# UPDuino_Camera_Adapter_2_himax.net
KiCad netlist of a schematic drawn in EAGLE
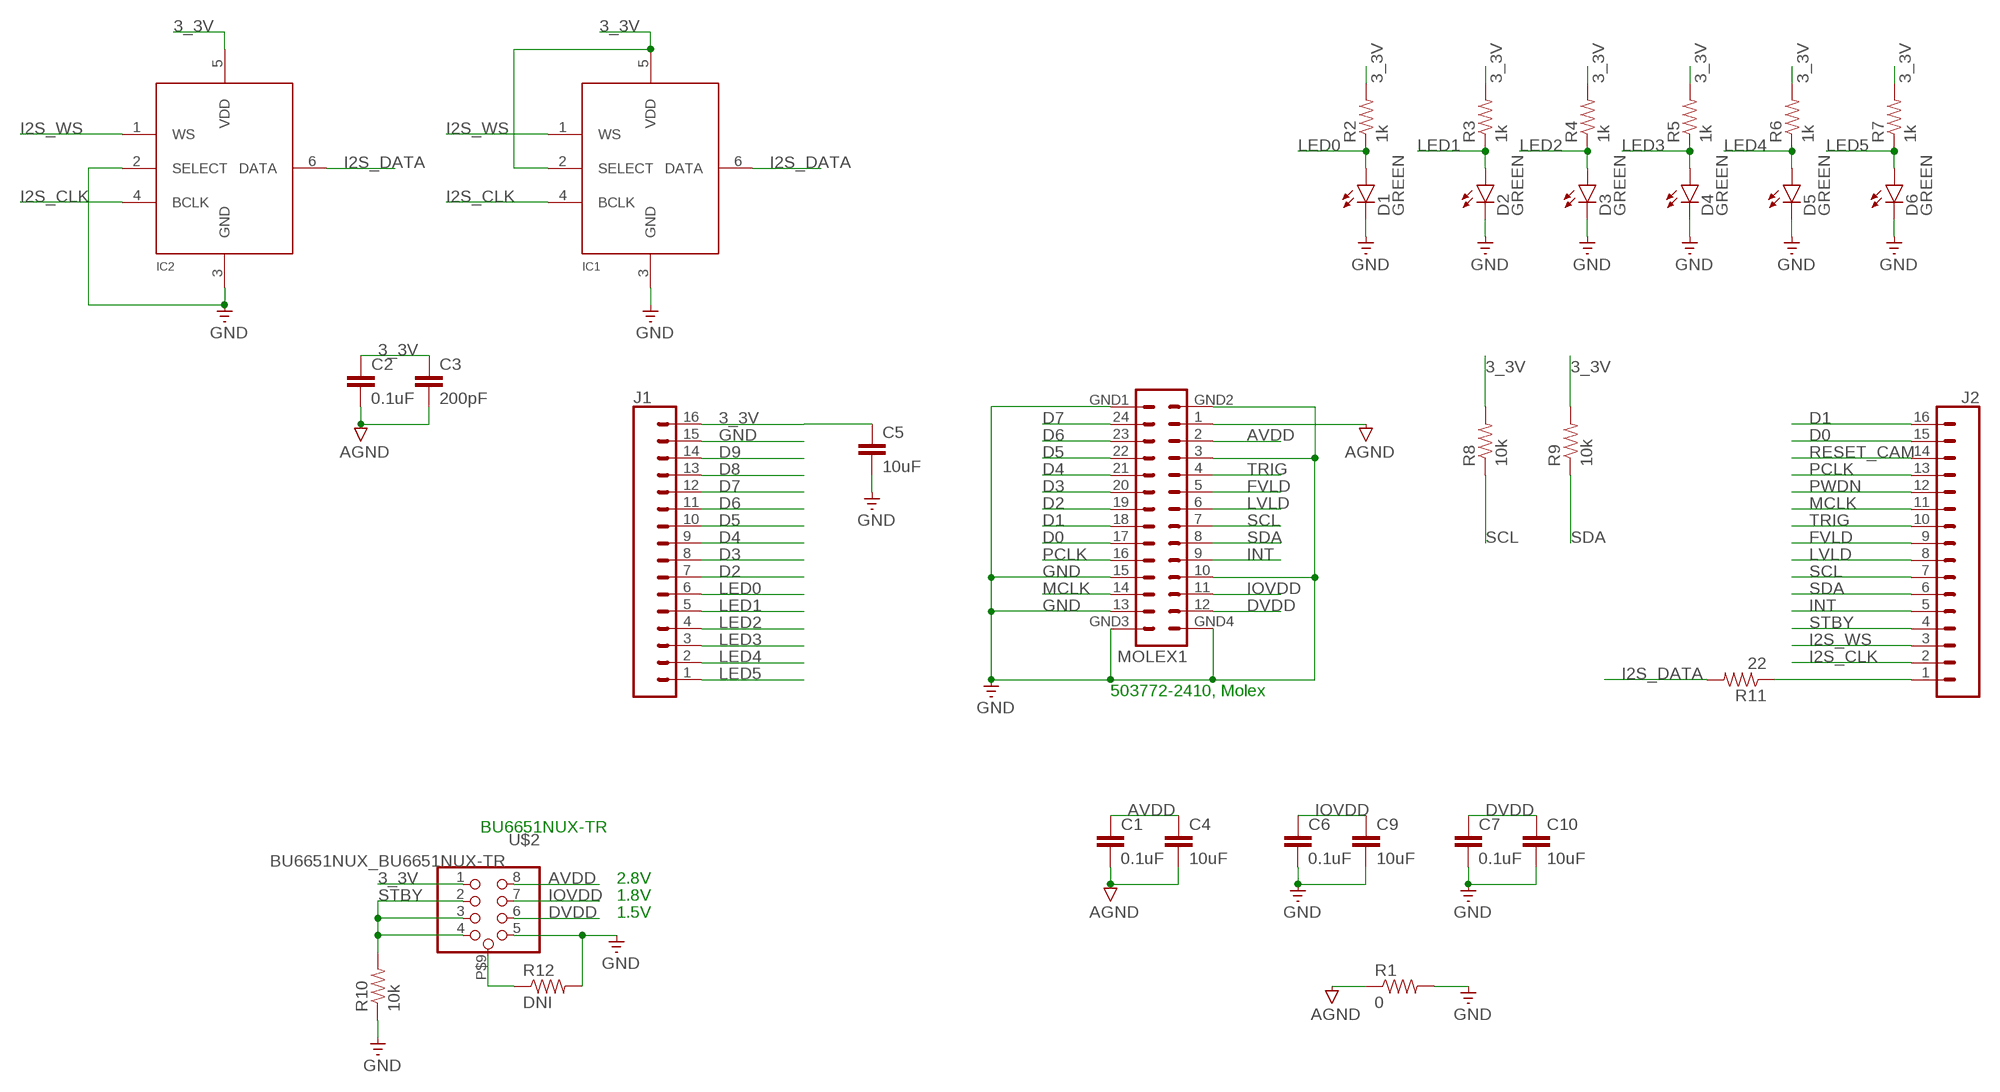
[diagram p0: schematic, sheet 1]

(export (version "E")
  (design (tool "Eeschema 10.0.6"))
  (components
    (comp (ref "C1")
      (value "0.1uF")
      (footprint "eagle-import:0603")
      (libsource (lib "eagle-import") (part "0.1UF-0603-25V-(+80/-20%)"))
    )
    (comp (ref "C2")
      (value "0.1uF")
      (footprint "eagle-import:0603")
      (libsource (lib "eagle-import") (part "0.1UF-0603-25V-(+80/-20%)"))
    )
    (comp (ref "C3")
      (value "200pF")
      (footprint "eagle-import:0603")
      (libsource (lib "eagle-import") (part "10UF-0603-6.3V-20%"))
    )
    (comp (ref "C4")
      (value "10uF")
      (footprint "eagle-import:0603")
      (libsource (lib "eagle-import") (part "10UF-0603-6.3V-20%"))
    )
    (comp (ref "C5")
      (value "10uF")
      (footprint "eagle-import:0603")
      (libsource (lib "eagle-import") (part "10UF-0603-6.3V-20%"))
    )
    (comp (ref "C6")
      (value "0.1uF")
      (footprint "eagle-import:0603")
      (libsource (lib "eagle-import") (part "0.1UF-0603-25V-(+80/-20%)"))
    )
    (comp (ref "C7")
      (value "0.1uF")
      (footprint "eagle-import:0603")
      (libsource (lib "eagle-import") (part "0.1UF-0603-25V-(+80/-20%)"))
    )
    (comp (ref "C9")
      (value "10uF")
      (footprint "eagle-import:0603")
      (libsource (lib "eagle-import") (part "10UF-0603-6.3V-20%"))
    )
    (comp (ref "C10")
      (value "10uF")
      (footprint "eagle-import:0603")
      (libsource (lib "eagle-import") (part "10UF-0603-6.3V-20%"))
    )
    (comp (ref "D1")
      (value "GREEN")
      (footprint "eagle-import:LED-0603")
      (libsource (lib "eagle-import") (part "LED-GREEN0603"))
    )
    (comp (ref "D2")
      (value "GREEN")
      (footprint "eagle-import:LED-0603")
      (libsource (lib "eagle-import") (part "LED-GREEN0603"))
    )
    (comp (ref "D3")
      (value "GREEN")
      (footprint "eagle-import:LED-0603")
      (libsource (lib "eagle-import") (part "LED-GREEN0603"))
    )
    (comp (ref "D4")
      (value "GREEN")
      (footprint "eagle-import:LED-0603")
      (libsource (lib "eagle-import") (part "LED-GREEN0603"))
    )
    (comp (ref "D5")
      (value "GREEN")
      (footprint "eagle-import:LED-0603")
      (libsource (lib "eagle-import") (part "LED-GREEN0603"))
    )
    (comp (ref "D6")
      (value "GREEN")
      (footprint "eagle-import:LED-0603")
      (libsource (lib "eagle-import") (part "LED-GREEN0603"))
    )
    (comp (ref "IC1")
      (value "MIC_I2S_SPH0645")
      (footprint "eagle-import:SPH0645LM4H")
      (libsource (lib "eagle-import") (part "MIC_I2S_SPH0645"))
    )
    (comp (ref "IC2")
      (value "MIC_I2S_SPH0645")
      (footprint "eagle-import:SPH0645LM4H")
      (libsource (lib "eagle-import") (part "MIC_I2S_SPH0645"))
    )
    (comp (ref "J1")
      (value "CONN_16")
      (footprint "eagle-import:1X16")
      (libsource (lib "eagle-import") (part "CONN_16"))
    )
    (comp (ref "J2")
      (value "CONN_16")
      (footprint "eagle-import:1X16")
      (libsource (lib "eagle-import") (part "CONN_16"))
    )
    (comp (ref "MOLEX1")
      (value "MOLEX-5037722410_MOLEX")
      (footprint "eagle-import:MOLEX-5037722410_MOLEX")
      (libsource (lib "eagle-import") (part "MOLEX-5037722410_MOLEX"))
    )
    (comp (ref "R1")
      (value "0")
      (footprint "eagle-import:0603-RES")
      (libsource (lib "eagle-import") (part "RESISTOR0603"))
    )
    (comp (ref "R2")
      (value "1k")
      (footprint "eagle-import:0603-RES")
      (libsource (lib "eagle-import") (part "RESISTOR0603"))
    )
    (comp (ref "R3")
      (value "1k")
      (footprint "eagle-import:0603-RES")
      (libsource (lib "eagle-import") (part "RESISTOR0603"))
    )
    (comp (ref "R4")
      (value "1k")
      (footprint "eagle-import:0603-RES")
      (libsource (lib "eagle-import") (part "RESISTOR0603"))
    )
    (comp (ref "R5")
      (value "1k")
      (footprint "eagle-import:0603-RES")
      (libsource (lib "eagle-import") (part "RESISTOR0603"))
    )
    (comp (ref "R6")
      (value "1k")
      (footprint "eagle-import:0603-RES")
      (libsource (lib "eagle-import") (part "RESISTOR0603"))
    )
    (comp (ref "R7")
      (value "1k")
      (footprint "eagle-import:0603-RES")
      (libsource (lib "eagle-import") (part "RESISTOR0603"))
    )
    (comp (ref "R8")
      (value "10k")
      (footprint "eagle-import:0603-RES")
      (libsource (lib "eagle-import") (part "RESISTOR0603"))
    )
    (comp (ref "R9")
      (value "10k")
      (footprint "eagle-import:0603-RES")
      (libsource (lib "eagle-import") (part "RESISTOR0603"))
    )
    (comp (ref "R10")
      (value "10k")
      (footprint "eagle-import:0603-RES")
      (libsource (lib "eagle-import") (part "RESISTOR0603"))
    )
    (comp (ref "R11")
      (value "22")
      (footprint "eagle-import:0603-RES")
      (libsource (lib "eagle-import") (part "RESISTOR0603"))
    )
    (comp (ref "R12")
      (value "DNI")
      (footprint "eagle-import:0603-RES")
      (libsource (lib "eagle-import") (part "RESISTOR0603"))
    )
    (comp (ref "U$2")
      (value "BU6651NUX_BU6651NUX-TR")
      (footprint "eagle-import:BU6651NUX_BU6651NUX-TR")
      (libsource (lib "eagle-import") (part "BU6651NUX_BU6651NUX-TR"))
    )
  )
  (nets
    (net (code "1") (name "/3_3V") (class "Default")
      (node (ref "C2") (pin "1") (pinfunction "1_1") (pintype "passive"))
      (node (ref "C3") (pin "1") (pinfunction "1_1") (pintype "passive"))
      (node (ref "C5") (pin "1") (pinfunction "1_1") (pintype "passive"))
      (node (ref "IC1") (pin "2") (pinfunction "SELECT_2") (pintype "input"))
      (node (ref "IC1") (pin "5") (pinfunction "VDD_5") (pintype "power_in"))
      (node (ref "IC2") (pin "5") (pinfunction "VDD_5") (pintype "power_in"))
      (node (ref "J1") (pin "16") (pinfunction "16_16") (pintype "passive"))
      (node (ref "R2") (pin "2") (pinfunction "2_2") (pintype "passive"))
      (node (ref "R3") (pin "2") (pinfunction "2_2") (pintype "passive"))
      (node (ref "R4") (pin "2") (pinfunction "2_2") (pintype "passive"))
      (node (ref "R5") (pin "2") (pinfunction "2_2") (pintype "passive"))
      (node (ref "R6") (pin "2") (pinfunction "2_2") (pintype "passive"))
      (node (ref "R7") (pin "2") (pinfunction "2_2") (pintype "passive"))
      (node (ref "R8") (pin "2") (pinfunction "2_2") (pintype "passive"))
      (node (ref "R9") (pin "2") (pinfunction "2_2") (pintype "passive"))
      (node (ref "U$2") (pin "1") (pinfunction "8_1") (pintype "passive"))
    )
    (net (code "2") (name "/AVDD") (class "Default")
      (node (ref "C1") (pin "1") (pinfunction "1_1") (pintype "passive"))
      (node (ref "C4") (pin "1") (pinfunction "1_1") (pintype "passive"))
      (node (ref "MOLEX1") (pin "2") (pinfunction "2_2") (pintype "passive"))
      (node (ref "U$2") (pin "8") (pinfunction "1_8") (pintype "passive"))
    )
    (net (code "3") (name "/D0") (class "Default")
      (node (ref "J2") (pin "15") (pinfunction "15_15") (pintype "passive"))
      (node (ref "MOLEX1") (pin "17") (pinfunction "17_17") (pintype "passive"))
    )
    (net (code "4") (name "/D1") (class "Default")
      (node (ref "J2") (pin "16") (pinfunction "16_16") (pintype "passive"))
      (node (ref "MOLEX1") (pin "18") (pinfunction "18_18") (pintype "passive"))
    )
    (net (code "5") (name "/D2") (class "Default")
      (node (ref "J1") (pin "7") (pinfunction "7_7") (pintype "passive"))
      (node (ref "MOLEX1") (pin "19") (pinfunction "19_19") (pintype "passive"))
    )
    (net (code "6") (name "/D3") (class "Default")
      (node (ref "J1") (pin "8") (pinfunction "8_8") (pintype "passive"))
      (node (ref "MOLEX1") (pin "20") (pinfunction "20_20") (pintype "passive"))
    )
    (net (code "7") (name "/D4") (class "Default")
      (node (ref "J1") (pin "9") (pinfunction "9_9") (pintype "passive"))
      (node (ref "MOLEX1") (pin "21") (pinfunction "21_21") (pintype "passive"))
    )
    (net (code "8") (name "/D5") (class "Default")
      (node (ref "J1") (pin "10") (pinfunction "10_10") (pintype "passive"))
      (node (ref "MOLEX1") (pin "22") (pinfunction "22_22") (pintype "passive"))
    )
    (net (code "9") (name "/D6") (class "Default")
      (node (ref "J1") (pin "11") (pinfunction "11_11") (pintype "passive"))
      (node (ref "MOLEX1") (pin "23") (pinfunction "23_23") (pintype "passive"))
    )
    (net (code "10") (name "/D7") (class "Default")
      (node (ref "J1") (pin "12") (pinfunction "12_12") (pintype "passive"))
      (node (ref "MOLEX1") (pin "24") (pinfunction "24_24") (pintype "passive"))
    )
    (net (code "11") (name "/D8") (class "Default")
      (node (ref "J1") (pin "13") (pinfunction "13_13") (pintype "passive"))
    )
    (net (code "12") (name "/D9") (class "Default")
      (node (ref "J1") (pin "14") (pinfunction "14_14") (pintype "passive"))
    )
    (net (code "13") (name "/DVDD") (class "Default")
      (node (ref "C10") (pin "1") (pinfunction "1_1") (pintype "passive"))
      (node (ref "C7") (pin "1") (pinfunction "1_1") (pintype "passive"))
      (node (ref "MOLEX1") (pin "12") (pinfunction "12_12") (pintype "passive"))
      (node (ref "U$2") (pin "6") (pinfunction "3_6") (pintype "passive"))
    )
    (net (code "14") (name "/FVLD") (class "Default")
      (node (ref "J2") (pin "9") (pinfunction "9_9") (pintype "passive"))
      (node (ref "MOLEX1") (pin "5") (pinfunction "5_5") (pintype "passive"))
    )
    (net (code "15") (name "/I2S_CLK") (class "Default")
      (node (ref "IC1") (pin "4") (pinfunction "BCLK_4") (pintype "input"))
      (node (ref "IC2") (pin "4") (pinfunction "BCLK_4") (pintype "input"))
      (node (ref "J2") (pin "2") (pinfunction "2_2") (pintype "passive"))
    )
    (net (code "16") (name "/I2S_DATA") (class "Default")
      (node (ref "IC1") (pin "6") (pinfunction "DATA_6") (pintype "output"))
      (node (ref "IC2") (pin "6") (pinfunction "DATA_6") (pintype "output"))
      (node (ref "R11") (pin "2") (pinfunction "2_2") (pintype "passive"))
    )
    (net (code "17") (name "/I2S_WS") (class "Default")
      (node (ref "IC1") (pin "1") (pinfunction "WS_1") (pintype "input"))
      (node (ref "IC2") (pin "1") (pinfunction "WS_1") (pintype "input"))
      (node (ref "J2") (pin "3") (pinfunction "3_3") (pintype "passive"))
    )
    (net (code "18") (name "/INT") (class "Default")
      (node (ref "J2") (pin "5") (pinfunction "5_5") (pintype "passive"))
      (node (ref "MOLEX1") (pin "9") (pinfunction "9_9") (pintype "passive"))
    )
    (net (code "19") (name "/IOVDD") (class "Default")
      (node (ref "C6") (pin "1") (pinfunction "1_1") (pintype "passive"))
      (node (ref "C9") (pin "1") (pinfunction "1_1") (pintype "passive"))
      (node (ref "MOLEX1") (pin "11") (pinfunction "11_11") (pintype "passive"))
      (node (ref "U$2") (pin "7") (pinfunction "2_7") (pintype "passive"))
    )
    (net (code "20") (name "/LED0") (class "Default")
      (node (ref "D1") (pin "A") (pinfunction "A_A") (pintype "passive"))
      (node (ref "J1") (pin "6") (pinfunction "6_6") (pintype "passive"))
      (node (ref "R2") (pin "1") (pinfunction "1_1") (pintype "passive"))
    )
    (net (code "21") (name "/LED1") (class "Default")
      (node (ref "D2") (pin "A") (pinfunction "A_A") (pintype "passive"))
      (node (ref "J1") (pin "5") (pinfunction "5_5") (pintype "passive"))
      (node (ref "R3") (pin "1") (pinfunction "1_1") (pintype "passive"))
    )
    (net (code "22") (name "/LED2") (class "Default")
      (node (ref "D3") (pin "A") (pinfunction "A_A") (pintype "passive"))
      (node (ref "J1") (pin "4") (pinfunction "4_4") (pintype "passive"))
      (node (ref "R4") (pin "1") (pinfunction "1_1") (pintype "passive"))
    )
    (net (code "23") (name "/LED3") (class "Default")
      (node (ref "D4") (pin "A") (pinfunction "A_A") (pintype "passive"))
      (node (ref "J1") (pin "3") (pinfunction "3_3") (pintype "passive"))
      (node (ref "R5") (pin "1") (pinfunction "1_1") (pintype "passive"))
    )
    (net (code "24") (name "/LED4") (class "Default")
      (node (ref "D5") (pin "A") (pinfunction "A_A") (pintype "passive"))
      (node (ref "J1") (pin "2") (pinfunction "2_2") (pintype "passive"))
      (node (ref "R6") (pin "1") (pinfunction "1_1") (pintype "passive"))
    )
    (net (code "25") (name "/LED5") (class "Default")
      (node (ref "D6") (pin "A") (pinfunction "A_A") (pintype "passive"))
      (node (ref "J1") (pin "1") (pinfunction "1_1") (pintype "passive"))
      (node (ref "R7") (pin "1") (pinfunction "1_1") (pintype "passive"))
    )
    (net (code "26") (name "/LVLD") (class "Default")
      (node (ref "J2") (pin "8") (pinfunction "8_8") (pintype "passive"))
      (node (ref "MOLEX1") (pin "6") (pinfunction "6_6") (pintype "passive"))
    )
    (net (code "27") (name "/MCLK") (class "Default")
      (node (ref "J2") (pin "11") (pinfunction "11_11") (pintype "passive"))
      (node (ref "MOLEX1") (pin "14") (pinfunction "14_14") (pintype "passive"))
    )
    (net (code "28") (name "/PCLK") (class "Default")
      (node (ref "J2") (pin "13") (pinfunction "13_13") (pintype "passive"))
      (node (ref "MOLEX1") (pin "16") (pinfunction "16_16") (pintype "passive"))
    )
    (net (code "29") (name "/PWDN") (class "Default")
      (node (ref "J2") (pin "12") (pinfunction "12_12") (pintype "passive"))
    )
    (net (code "30") (name "/RESET_CAM") (class "Default")
      (node (ref "J2") (pin "14") (pinfunction "14_14") (pintype "passive"))
    )
    (net (code "31") (name "/SCL") (class "Default")
      (node (ref "J2") (pin "7") (pinfunction "7_7") (pintype "passive"))
      (node (ref "MOLEX1") (pin "7") (pinfunction "7_7") (pintype "passive"))
      (node (ref "R8") (pin "1") (pinfunction "1_1") (pintype "passive"))
    )
    (net (code "32") (name "/SDA") (class "Default")
      (node (ref "J2") (pin "6") (pinfunction "6_6") (pintype "passive"))
      (node (ref "MOLEX1") (pin "8") (pinfunction "8_8") (pintype "passive"))
      (node (ref "R9") (pin "1") (pinfunction "1_1") (pintype "passive"))
    )
    (net (code "33") (name "/STBY") (class "Default")
      (node (ref "J2") (pin "4") (pinfunction "4_4") (pintype "passive"))
      (node (ref "R10") (pin "2") (pinfunction "2_2") (pintype "passive"))
      (node (ref "U$2") (pin "2") (pinfunction "7_2") (pintype "passive"))
      (node (ref "U$2") (pin "3") (pinfunction "6_3") (pintype "passive"))
      (node (ref "U$2") (pin "4") (pinfunction "5_4") (pintype "passive"))
    )
    (net (code "34") (name "/TRIG") (class "Default")
      (node (ref "J2") (pin "10") (pinfunction "10_10") (pintype "passive"))
      (node (ref "MOLEX1") (pin "4") (pinfunction "4_4") (pintype "passive"))
    )
    (net (code "35") (name "AGND") (class "Default")
      (node (ref "C1") (pin "2") (pinfunction "2_2") (pintype "passive"))
      (node (ref "C2") (pin "2") (pinfunction "2_2") (pintype "passive"))
      (node (ref "C3") (pin "2") (pinfunction "2_2") (pintype "passive"))
      (node (ref "C4") (pin "2") (pinfunction "2_2") (pintype "passive"))
      (node (ref "MOLEX1") (pin "1") (pinfunction "1_1") (pintype "passive"))
      (node (ref "R1") (pin "1") (pinfunction "1_1") (pintype "passive"))
    )
    (net (code "36") (name "GND") (class "Default")
      (node (ref "C10") (pin "2") (pinfunction "2_2") (pintype "passive"))
      (node (ref "C5") (pin "2") (pinfunction "2_2") (pintype "passive"))
      (node (ref "C6") (pin "2") (pinfunction "2_2") (pintype "passive"))
      (node (ref "C7") (pin "2") (pinfunction "2_2") (pintype "passive"))
      (node (ref "C9") (pin "2") (pinfunction "2_2") (pintype "passive"))
      (node (ref "D1") (pin "C") (pinfunction "C_C") (pintype "passive"))
      (node (ref "D2") (pin "C") (pinfunction "C_C") (pintype "passive"))
      (node (ref "D3") (pin "C") (pinfunction "C_C") (pintype "passive"))
      (node (ref "D4") (pin "C") (pinfunction "C_C") (pintype "passive"))
      (node (ref "D5") (pin "C") (pinfunction "C_C") (pintype "passive"))
      (node (ref "D6") (pin "C") (pinfunction "C_C") (pintype "passive"))
      (node (ref "IC1") (pin "3") (pinfunction "GND_3") (pintype "power_in"))
      (node (ref "IC2") (pin "2") (pinfunction "SELECT_2") (pintype "input"))
      (node (ref "IC2") (pin "3") (pinfunction "GND_3") (pintype "power_in"))
      (node (ref "J1") (pin "15") (pinfunction "15_15") (pintype "passive"))
      (node (ref "MOLEX1") (pin "10") (pinfunction "10_10") (pintype "passive"))
      (node (ref "MOLEX1") (pin "13") (pinfunction "13_13") (pintype "passive"))
      (node (ref "MOLEX1") (pin "15") (pinfunction "15_15") (pintype "passive"))
      (node (ref "MOLEX1") (pin "3") (pinfunction "3_3") (pintype "passive"))
      (node (ref "MOLEX1") (pin "GND1") (pinfunction "GND1_GND1") (pintype "passive"))
      (node (ref "MOLEX1") (pin "GND2") (pinfunction "GND2_GND2") (pintype "passive"))
      (node (ref "MOLEX1") (pin "GND3") (pinfunction "GND3_GND3") (pintype "passive"))
      (node (ref "MOLEX1") (pin "GND4") (pinfunction "GND4_GND4") (pintype "passive"))
      (node (ref "R1") (pin "2") (pinfunction "2_2") (pintype "passive"))
      (node (ref "R10") (pin "1") (pinfunction "1_1") (pintype "passive"))
      (node (ref "R12") (pin "2") (pinfunction "2_2") (pintype "passive"))
      (node (ref "U$2") (pin "5") (pinfunction "4_5") (pintype "passive"))
    )
    (net (code "37") (name "Net-(J2-Pad1)") (class "Default")
      (node (ref "J2") (pin "1") (pinfunction "1_1") (pintype "passive"))
      (node (ref "R11") (pin "1") (pinfunction "1_1") (pintype "passive"))
    )
    (net (code "38") (name "Net-(U$2-9)") (class "Default")
      (node (ref "R12") (pin "1") (pinfunction "1_1") (pintype "passive"))
      (node (ref "U$2") (pin "P$9") (pinfunction "9_P$9") (pintype "passive"))
    )
  )
)
